# mm-001.net
KiCad netlist of a schematic drawn in EAGLE
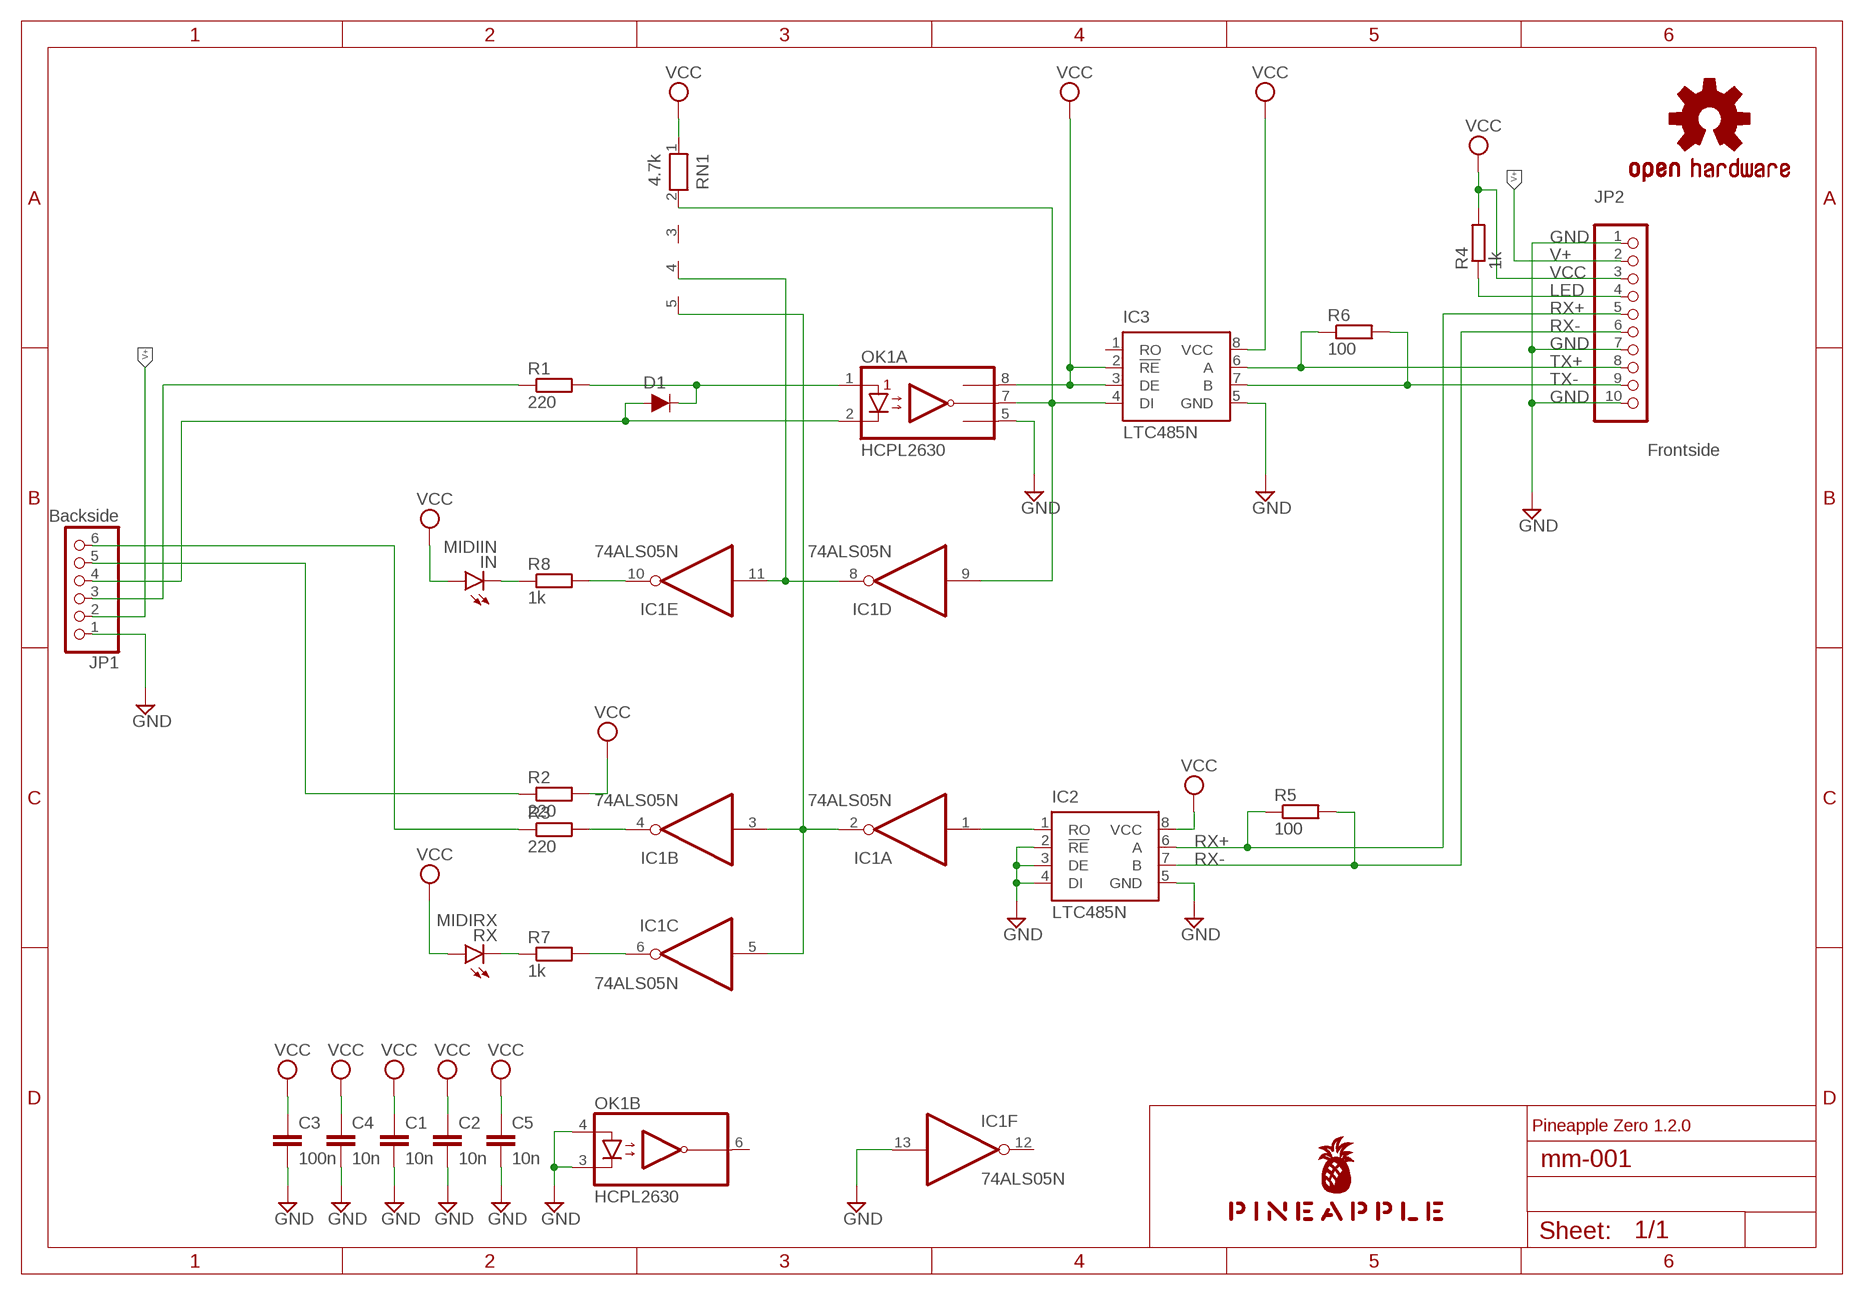
[diagram p0: schematic, sheet 1]

(export (version "E")
  (design (tool "Eeschema 10.0.6"))
  (components
    (comp (ref "C1")
      (value "10n")
      (footprint "eagle-import:C025-024X044")
      (libsource (lib "eagle-import") (part "C-EU025-024X044"))
    )
    (comp (ref "C2")
      (value "10n")
      (footprint "eagle-import:C025-024X044")
      (libsource (lib "eagle-import") (part "C-EU025-024X044"))
    )
    (comp (ref "C3")
      (value "100n")
      (footprint "eagle-import:C025-024X044")
      (libsource (lib "eagle-import") (part "C-EU025-024X044"))
    )
    (comp (ref "C4")
      (value "10n")
      (footprint "eagle-import:C025-024X044")
      (libsource (lib "eagle-import") (part "C-EU025-024X044"))
    )
    (comp (ref "C5")
      (value "10n")
      (footprint "eagle-import:C025-024X044")
      (libsource (lib "eagle-import") (part "C-EU025-024X044"))
    )
    (comp (ref "D1")
      (value "DIODE-1N4148")
      (footprint "eagle-import:DIODE-1N4148")
      (libsource (lib "eagle-import") (part "DIODE-1N4148"))
    )
    (comp (ref "IC1")
      (value "74ALS05N")
      (footprint "eagle-import:DIL14")
      (libsource (lib "eagle-import") (part "7405NALS"))
    )
    (comp (ref "IC2")
      (value "LTC485N")
      (footprint "eagle-import:DIL08")
      (libsource (lib "eagle-import") (part "LTC485N"))
    )
    (comp (ref "IC3")
      (value "LTC485N")
      (footprint "eagle-import:DIL08")
      (libsource (lib "eagle-import") (part "LTC485N"))
    )
    (comp (ref "IN")
      (value "MIDIIN")
      (footprint "eagle-import:LED3MM")
      (libsource (lib "eagle-import") (part "LED3MM"))
    )
    (comp (ref "JP1")
      (value "Backside")
      (footprint "eagle-import:1X06")
      (libsource (lib "eagle-import") (part "PINHD-1X6"))
    )
    (comp (ref "JP2")
      (value "Frontside")
      (footprint "eagle-import:1X10")
      (libsource (lib "eagle-import") (part "PINHD-1X10"))
    )
    (comp (ref "LOGO1")
      (value "OSHW-LOGOS-COPPER")
      (footprint "eagle-import:OSHW-LOGO-S_COPPER")
      (libsource (lib "eagle-import") (part "OSHW-LOGOS-COPPER"))
    )
    (comp (ref "OK1")
      (value "HCPL2630")
      (footprint "eagle-import:DIL08")
      (fields (field (name "MF") "AGILENT TECHNOLOGIES") (field (name "MPN") "HCPL-2630-000E"))
      (libsource (lib "eagle-import") (part "HCPL2630"))
    )
    (comp (ref "R1")
      (value "220")
      (footprint "eagle-import:0204_5")
      (libsource (lib "eagle-import") (part "R-EU_0204/5"))
    )
    (comp (ref "R2")
      (value "220")
      (footprint "eagle-import:0204_5")
      (libsource (lib "eagle-import") (part "R-EU_0204/5"))
    )
    (comp (ref "R3")
      (value "220")
      (footprint "eagle-import:0204_5")
      (libsource (lib "eagle-import") (part "R-EU_0204/5"))
    )
    (comp (ref "R4")
      (value "1k")
      (footprint "eagle-import:0204_5")
      (libsource (lib "eagle-import") (part "R-EU_0204/5"))
    )
    (comp (ref "R5")
      (value "100")
      (footprint "eagle-import:0204_5")
      (libsource (lib "eagle-import") (part "R-EU_0204/5"))
    )
    (comp (ref "R6")
      (value "100")
      (footprint "eagle-import:0204_5")
      (libsource (lib "eagle-import") (part "R-EU_0204/5"))
    )
    (comp (ref "R7")
      (value "1k")
      (footprint "eagle-import:0204_5")
      (libsource (lib "eagle-import") (part "R-EU_0204/5"))
    )
    (comp (ref "R8")
      (value "1k")
      (footprint "eagle-import:0204_5")
      (libsource (lib "eagle-import") (part "R-EU_0204/5"))
    )
    (comp (ref "RN1")
      (value "4.7k")
      (footprint "eagle-import:RN-5")
      (libsource (lib "eagle-import") (part "RN04"))
    )
    (comp (ref "RX")
      (value "MIDIRX")
      (footprint "eagle-import:LED3MM")
      (libsource (lib "eagle-import") (part "LED3MM"))
    )
    (comp (ref "U$1")
      (value "PINEAPPLE450")
      (footprint "eagle-import:PINEAPPLE450")
      (libsource (lib "eagle-import") (part "PINEAPPLE450"))
    )
  )
  (nets
    (net (code "1") (name "/LED") (class "Default")
      (node (ref "JP2") (pin "4") (pinfunction "4_4") (pintype "passive"))
      (node (ref "R4") (pin "1") (pinfunction "1_1") (pintype "passive"))
    )
    (net (code "2") (name "/RX+") (class "Default")
      (node (ref "IC2") (pin "6") (pinfunction "A_6") (pintype "bidirectional"))
      (node (ref "JP2") (pin "5") (pinfunction "5_5") (pintype "passive"))
      (node (ref "R5") (pin "1") (pinfunction "1_1") (pintype "passive"))
    )
    (net (code "3") (name "/RX-") (class "Default")
      (node (ref "IC2") (pin "7") (pinfunction "B_7") (pintype "bidirectional"))
      (node (ref "JP2") (pin "6") (pinfunction "6_6") (pintype "passive"))
      (node (ref "R5") (pin "2") (pinfunction "2_2") (pintype "passive"))
    )
    (net (code "4") (name "/TX+") (class "Default")
      (node (ref "IC3") (pin "6") (pinfunction "A_6") (pintype "bidirectional"))
      (node (ref "JP2") (pin "8") (pinfunction "8_8") (pintype "passive"))
      (node (ref "R6") (pin "1") (pinfunction "1_1") (pintype "passive"))
    )
    (net (code "5") (name "/TX-") (class "Default")
      (node (ref "IC3") (pin "7") (pinfunction "B_7") (pintype "bidirectional"))
      (node (ref "JP2") (pin "9") (pinfunction "9_9") (pintype "passive"))
      (node (ref "R6") (pin "2") (pinfunction "2_2") (pintype "passive"))
    )
    (net (code "6") (name "GND") (class "Default")
      (node (ref "C1") (pin "2") (pinfunction "2_2") (pintype "passive"))
      (node (ref "C2") (pin "2") (pinfunction "2_2") (pintype "passive"))
      (node (ref "C3") (pin "2") (pinfunction "2_2") (pintype "passive"))
      (node (ref "C4") (pin "2") (pinfunction "2_2") (pintype "passive"))
      (node (ref "C5") (pin "2") (pinfunction "2_2") (pintype "passive"))
      (node (ref "IC1") (pin "13") (pinfunction "I_13") (pintype "input"))
      (node (ref "IC2") (pin "2") (pinfunction "~{RE}_2") (pintype "input"))
      (node (ref "IC2") (pin "3") (pinfunction "DE_3") (pintype "input"))
      (node (ref "IC2") (pin "4") (pinfunction "DI_4") (pintype "input"))
      (node (ref "IC2") (pin "5") (pinfunction "GND_5") (pintype "input"))
      (node (ref "IC3") (pin "5") (pinfunction "GND_5") (pintype "input"))
      (node (ref "JP1") (pin "1") (pinfunction "1_1") (pintype "passive"))
      (node (ref "JP2") (pin "1") (pinfunction "1_1") (pintype "passive"))
      (node (ref "JP2") (pin "10") (pinfunction "10_10") (pintype "passive"))
      (node (ref "JP2") (pin "7") (pinfunction "7_7") (pintype "passive"))
      (node (ref "OK1") (pin "3") (pinfunction "C2_3") (pintype "passive"))
      (node (ref "OK1") (pin "4") (pinfunction "A2_4") (pintype "passive"))
      (node (ref "OK1") (pin "5") (pinfunction "GND_5") (pintype "passive"))
    )
    (net (code "7") (name "Net-(IC1A-I)") (class "Default")
      (node (ref "IC1") (pin "1") (pinfunction "I_1") (pintype "input"))
      (node (ref "IC2") (pin "1") (pinfunction "RO_1") (pintype "output"))
    )
    (net (code "8") (name "Net-(IC1A-O)") (class "Default")
      (node (ref "IC1") (pin "2") (pinfunction "O_2") (pintype "open_collector"))
      (node (ref "IC1") (pin "3") (pinfunction "I_3") (pintype "input"))
      (node (ref "IC1") (pin "5") (pinfunction "I_5") (pintype "input"))
      (node (ref "RN1") (pin "5") (pinfunction "5_5") (pintype "passive"))
    )
    (net (code "9") (name "Net-(IC1B-O)") (class "Default")
      (node (ref "IC1") (pin "4") (pinfunction "O_4") (pintype "open_collector"))
      (node (ref "R3") (pin "2") (pinfunction "2_2") (pintype "passive"))
    )
    (net (code "10") (name "Net-(IC1C-O)") (class "Default")
      (node (ref "IC1") (pin "6") (pinfunction "O_6") (pintype "open_collector"))
      (node (ref "R7") (pin "2") (pinfunction "2_2") (pintype "passive"))
    )
    (net (code "11") (name "Net-(IC1D-I)") (class "Default")
      (node (ref "IC1") (pin "9") (pinfunction "I_9") (pintype "input"))
      (node (ref "IC3") (pin "4") (pinfunction "DI_4") (pintype "input"))
      (node (ref "OK1") (pin "7") (pinfunction "VO1_7") (pintype "passive"))
      (node (ref "RN1") (pin "2") (pinfunction "2_2") (pintype "passive"))
    )
    (net (code "12") (name "Net-(IC1D-O)") (class "Default")
      (node (ref "IC1") (pin "11") (pinfunction "I_11") (pintype "input"))
      (node (ref "IC1") (pin "8") (pinfunction "O_8") (pintype "open_collector"))
      (node (ref "RN1") (pin "4") (pinfunction "4_4") (pintype "passive"))
    )
    (net (code "13") (name "Net-(IC1E-O)") (class "Default")
      (node (ref "IC1") (pin "10") (pinfunction "O_10") (pintype "open_collector"))
      (node (ref "R8") (pin "2") (pinfunction "2_2") (pintype "passive"))
    )
    (net (code "14") (name "Net-(IN-C)") (class "Default")
      (node (ref "IN") (pin "K") (pinfunction "C_K") (pintype "passive"))
      (node (ref "R8") (pin "1") (pinfunction "1_1") (pintype "passive"))
    )
    (net (code "15") (name "Net-(JP1-Pad3)") (class "Default")
      (node (ref "JP1") (pin "3") (pinfunction "3_3") (pintype "passive"))
      (node (ref "R1") (pin "1") (pinfunction "1_1") (pintype "passive"))
    )
    (net (code "16") (name "Net-(JP1-Pad5)") (class "Default")
      (node (ref "JP1") (pin "5") (pinfunction "5_5") (pintype "passive"))
      (node (ref "R2") (pin "1") (pinfunction "1_1") (pintype "passive"))
    )
    (net (code "17") (name "Net-(JP1-Pad6)") (class "Default")
      (node (ref "JP1") (pin "6") (pinfunction "6_6") (pintype "passive"))
      (node (ref "R3") (pin "1") (pinfunction "1_1") (pintype "passive"))
    )
    (net (code "18") (name "Net-(OK1A-A1)") (class "Default")
      (node (ref "D1") (pin "C") (pinfunction "C_C") (pintype "passive"))
      (node (ref "OK1") (pin "1") (pinfunction "A1_1") (pintype "passive"))
      (node (ref "R1") (pin "2") (pinfunction "2_2") (pintype "passive"))
    )
    (net (code "19") (name "Net-(OK1A-C1)") (class "Default")
      (node (ref "D1") (pin "A") (pinfunction "A_A") (pintype "passive"))
      (node (ref "JP1") (pin "4") (pinfunction "4_4") (pintype "passive"))
      (node (ref "OK1") (pin "2") (pinfunction "C1_2") (pintype "passive"))
    )
    (net (code "20") (name "Net-(RX-C)") (class "Default")
      (node (ref "R7") (pin "1") (pinfunction "1_1") (pintype "passive"))
      (node (ref "RX") (pin "K") (pinfunction "C_K") (pintype "passive"))
    )
    (net (code "21") (name "V+") (class "Default")
      (node (ref "JP1") (pin "2") (pinfunction "2_2") (pintype "passive"))
      (node (ref "JP2") (pin "2") (pinfunction "2_2") (pintype "passive"))
    )
    (net (code "22") (name "VCC") (class "Default")
      (node (ref "C1") (pin "1") (pinfunction "1_1") (pintype "passive"))
      (node (ref "C2") (pin "1") (pinfunction "1_1") (pintype "passive"))
      (node (ref "C3") (pin "1") (pinfunction "1_1") (pintype "passive"))
      (node (ref "C4") (pin "1") (pinfunction "1_1") (pintype "passive"))
      (node (ref "C5") (pin "1") (pinfunction "1_1") (pintype "passive"))
      (node (ref "IC2") (pin "8") (pinfunction "VCC_8") (pintype "input"))
      (node (ref "IC3") (pin "2") (pinfunction "~{RE}_2") (pintype "input"))
      (node (ref "IC3") (pin "3") (pinfunction "DE_3") (pintype "input"))
      (node (ref "IC3") (pin "8") (pinfunction "VCC_8") (pintype "input"))
      (node (ref "IN") (pin "A") (pinfunction "A_A") (pintype "passive"))
      (node (ref "JP2") (pin "3") (pinfunction "3_3") (pintype "passive"))
      (node (ref "OK1") (pin "8") (pinfunction "VCC_8") (pintype "passive"))
      (node (ref "R2") (pin "2") (pinfunction "2_2") (pintype "passive"))
      (node (ref "R4") (pin "2") (pinfunction "2_2") (pintype "passive"))
      (node (ref "RN1") (pin "1") (pinfunction "1_1") (pintype "passive"))
      (node (ref "RX") (pin "A") (pinfunction "A_A") (pintype "passive"))
    )
    (net (code "23") (name "unconnected-(IC1F-O-Pad12)") (class "Default")
      (node (ref "IC1") (pin "12") (pinfunction "O_12") (pintype "open_collector"))
    )
    (net (code "24") (name "unconnected-(IC3-RO-Pad1)") (class "Default")
      (node (ref "IC3") (pin "1") (pinfunction "RO_1") (pintype "output"))
    )
    (net (code "25") (name "unconnected-(OK1B-VO2-Pad6)") (class "Default")
      (node (ref "OK1") (pin "6") (pinfunction "VO2_6") (pintype "passive"))
    )
    (net (code "26") (name "unconnected-(RN1-Pad3)") (class "Default")
      (node (ref "RN1") (pin "3") (pinfunction "3_3") (pintype "passive"))
    )
  )
)
